# tritiled_nocell.net
KiCad netlist of a schematic drawn in EAGLE
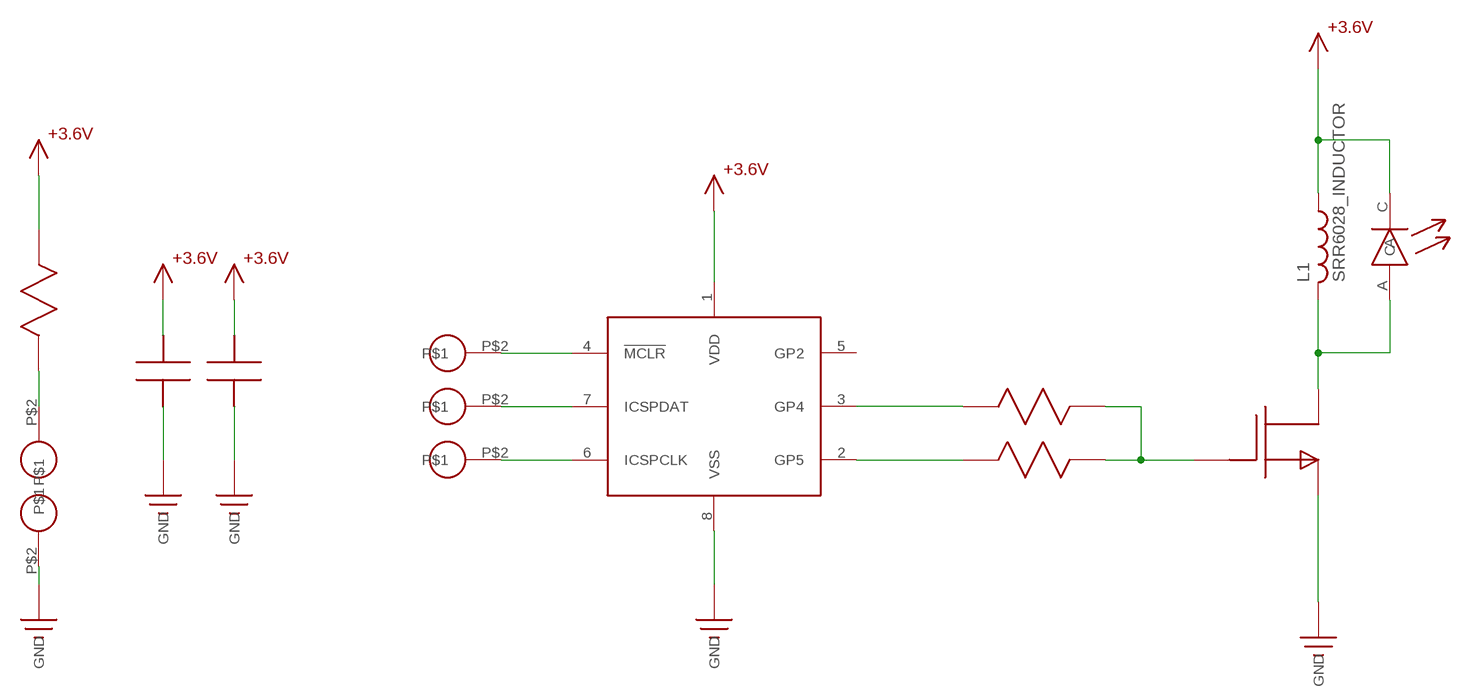
[diagram p0: schematic, sheet 1]

(export (version "E")
  (design (tool "Eeschema 10.0.6"))
  (components
    (comp (ref "L1")
      (value "SRR6028_INDUCTOR")
      (footprint "eagle-import:SRR6028_INDUCTOR")
      (libsource (lib "eagle-import") (part "SRR6028_INDUCTOR"))
    )
    (comp (ref "U$1")
      (value "PIC12LF1571")
      (footprint "eagle-import:SOIC8")
      (libsource (lib "eagle-import") (part "PIC12LF1571"))
    )
    (comp (ref "U$7")
      (value "ICSP_PAD")
      (footprint "eagle-import:ICSP_PAD")
      (libsource (lib "eagle-import") (part "ICSP_PAD"))
    )
    (comp (ref "U$9")
      (value "ICSP_PAD")
      (footprint "eagle-import:ICSP_PAD")
      (libsource (lib "eagle-import") (part "ICSP_PAD"))
    )
    (comp (ref "U$10")
      (value "R1206")
      (footprint "eagle-import:R1206")
      (libsource (lib "eagle-import") (part "R1206"))
    )
    (comp (ref "U$12")
      (value "LED_3W")
      (footprint "eagle-import:LED_3W")
      (libsource (lib "eagle-import") (part "LED_3W"))
    )
    (comp (ref "U$16")
      (value "ZXMN3B01FSOT23")
      (footprint "eagle-import:SOT-23")
      (libsource (lib "eagle-import") (part "ZXMN3B01FSOT23"))
    )
    (comp (ref "U$17")
      (value "ICSP_PAD")
      (footprint "eagle-import:ICSP_PAD")
      (libsource (lib "eagle-import") (part "ICSP_PAD"))
    )
    (comp (ref "U$18")
      (value "ICSP_PAD")
      (footprint "eagle-import:ICSP_PAD")
      (libsource (lib "eagle-import") (part "ICSP_PAD"))
    )
    (comp (ref "U$19")
      (value "ICSP_PAD")
      (footprint "eagle-import:ICSP_PAD")
      (libsource (lib "eagle-import") (part "ICSP_PAD"))
    )
    (comp (ref "U$20")
      (value "C1206")
      (footprint "eagle-import:1206")
      (libsource (lib "eagle-import") (part "C1206"))
    )
    (comp (ref "U$21")
      (value "C0603")
      (footprint "eagle-import:C0603")
      (libsource (lib "eagle-import") (part "C0603"))
    )
    (comp (ref "U$22")
      (value "R0603")
      (footprint "eagle-import:R0603")
      (libsource (lib "eagle-import") (part "R0603"))
    )
    (comp (ref "U$23")
      (value "R0603")
      (footprint "eagle-import:R0603")
      (libsource (lib "eagle-import") (part "R0603"))
    )
  )
  (nets
    (net (code "1") (name "+3.6V") (class "Default")
      (node (ref "L1") (pin "P$1") (pinfunction "1_P$1") (pintype "passive"))
      (node (ref "U$1") (pin "1") (pinfunction "VDD_1") (pintype "bidirectional"))
      (node (ref "U$10") (pin "P$1") (pinfunction "P$1_P$1") (pintype "bidirectional"))
      (node (ref "U$12") (pin "C") (pinfunction "C_C") (pintype "bidirectional"))
      (node (ref "U$20") (pin "P$1") (pinfunction "P$1_P$1") (pintype "bidirectional"))
      (node (ref "U$21") (pin "P$1") (pinfunction "P$1_P$1") (pintype "bidirectional"))
    )
    (net (code "2") (name "GND") (class "Default")
      (node (ref "U$1") (pin "8") (pinfunction "VSS_8") (pintype "bidirectional"))
      (node (ref "U$16") (pin "2") (pinfunction "S_2") (pintype "bidirectional"))
      (node (ref "U$20") (pin "P$2") (pinfunction "P$2_P$2") (pintype "bidirectional"))
      (node (ref "U$21") (pin "P$2") (pinfunction "P$2_P$2") (pintype "bidirectional"))
      (node (ref "U$9") (pin "P$2") (pinfunction "P$1_P$2") (pintype "bidirectional"))
    )
    (net (code "3") (name "Net-(L1-2)") (class "Default")
      (node (ref "L1") (pin "P$2") (pinfunction "2_P$2") (pintype "passive"))
      (node (ref "U$12") (pin "A") (pinfunction "A_A") (pintype "bidirectional"))
      (node (ref "U$16") (pin "3") (pinfunction "D_3") (pintype "bidirectional"))
    )
    (net (code "4") (name "Net-(U$1-GP4)") (class "Default")
      (node (ref "U$1") (pin "3") (pinfunction "GP4_3") (pintype "bidirectional"))
      (node (ref "U$23") (pin "P$1") (pinfunction "P$1_P$1") (pintype "bidirectional"))
    )
    (net (code "5") (name "Net-(U$1-GP5)") (class "Default")
      (node (ref "U$1") (pin "2") (pinfunction "GP5_2") (pintype "bidirectional"))
      (node (ref "U$22") (pin "P$1") (pinfunction "P$1_P$1") (pintype "bidirectional"))
    )
    (net (code "6") (name "Net-(U$1-ICSPCLK)") (class "Default")
      (node (ref "U$1") (pin "6") (pinfunction "ICSPCLK_6") (pintype "bidirectional"))
      (node (ref "U$17") (pin "P$2") (pinfunction "P$1_P$2") (pintype "bidirectional"))
    )
    (net (code "7") (name "Net-(U$1-ICSPDAT)") (class "Default")
      (node (ref "U$1") (pin "7") (pinfunction "ICSPDAT_7") (pintype "bidirectional"))
      (node (ref "U$19") (pin "P$2") (pinfunction "P$1_P$2") (pintype "bidirectional"))
    )
    (net (code "8") (name "Net-(U$1-~{MCLR})") (class "Default")
      (node (ref "U$1") (pin "4") (pinfunction "~{MCLR}_4") (pintype "bidirectional"))
      (node (ref "U$18") (pin "P$2") (pinfunction "P$1_P$2") (pintype "bidirectional"))
    )
    (net (code "9") (name "Net-(U$7-P$1)") (class "Default")
      (node (ref "U$10") (pin "P$2") (pinfunction "P$2_P$2") (pintype "bidirectional"))
      (node (ref "U$7") (pin "P$2") (pinfunction "P$1_P$2") (pintype "bidirectional"))
    )
    (net (code "10") (name "Net-(U$16-G)") (class "Default")
      (node (ref "U$16") (pin "1") (pinfunction "G_1") (pintype "bidirectional"))
      (node (ref "U$22") (pin "P$2") (pinfunction "P$2_P$2") (pintype "bidirectional"))
      (node (ref "U$23") (pin "P$2") (pinfunction "P$2_P$2") (pintype "bidirectional"))
    )
    (net (code "11") (name "unconnected-(U$1-GP2-Pad5)") (class "Default")
      (node (ref "U$1") (pin "5") (pinfunction "GP2_5") (pintype "bidirectional"))
    )
  )
)
